# Inputs.net
KiCad netlist of a schematic drawn in Altium Designer
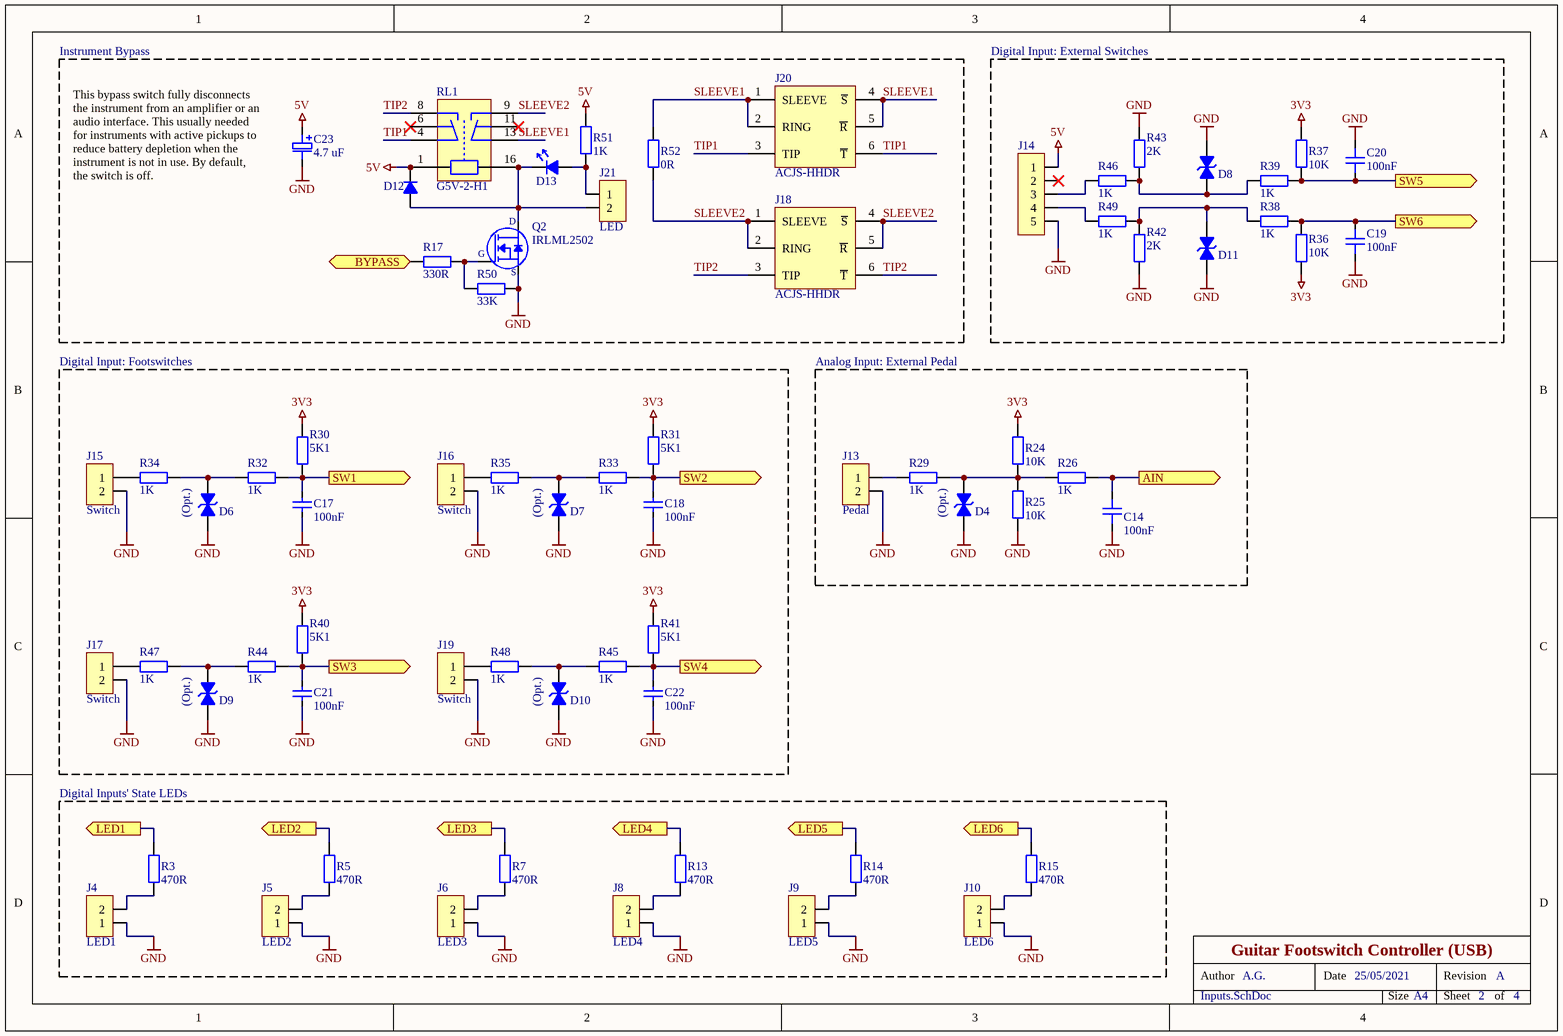
[diagram p0: Inputs.SchDoc]

(export (version "E")
  (design (tool "Eeschema 10.0.6"))
  (components
    (comp (ref "C14")
      (value "100nF")
      (footprint "0603C_RF_M")
      (description "Capacitor")
      (fields (field (name "TOLERANCE") "?") (field (name "MANUFACTURER") "Generic Brand"))
      (libsource (lib "") (part "C_1"))
    )
    (comp (ref "C17")
      (value "100nF")
      (footprint "0603C_RF_M")
      (description "Capacitor")
      (fields (field (name "TOLERANCE") "?") (field (name "MANUFACTURER") "Generic Brand"))
      (libsource (lib "AG.Generic") (part "C"))
    )
    (comp (ref "C18")
      (value "100nF")
      (footprint "0603C_RF_M")
      (description "Capacitor")
      (fields (field (name "TOLERANCE") "?") (field (name "MANUFACTURER") "Generic Brand"))
      (libsource (lib "AG.Generic") (part "C"))
    )
    (comp (ref "C19")
      (value "100nF")
      (footprint "0603C_RF_M")
      (description "Capacitor")
      (fields (field (name "TOLERANCE") "?") (field (name "MANUFACTURER") "Generic Brand"))
      (libsource (lib "") (part "C_1"))
    )
    (comp (ref "C20")
      (value "100nF")
      (footprint "0603C_RF_M")
      (description "Capacitor")
      (fields (field (name "TOLERANCE") "?") (field (name "MANUFACTURER") "Generic Brand"))
      (libsource (lib "") (part "C_1"))
    )
    (comp (ref "C21")
      (value "100nF")
      (footprint "0603C_RF_M")
      (description "Capacitor")
      (fields (field (name "TOLERANCE") "?") (field (name "MANUFACTURER") "Generic Brand"))
      (libsource (lib "AG.Generic") (part "C"))
    )
    (comp (ref "C22")
      (value "100nF")
      (footprint "0603C_RF_M")
      (description "Capacitor")
      (fields (field (name "TOLERANCE") "?") (field (name "MANUFACTURER") "Generic Brand"))
      (libsource (lib "AG.Generic") (part "C"))
    )
    (comp (ref "C23")
      (value "4.7 uF")
      (footprint "C_EL_B_4MM_RF_M")
      (description "Polarized Capacitor")
      (fields (field (name "TOLERANCE") "?") (field (name "MANUFACTURER") "Generic Brand"))
      (libsource (lib "AG.Generic") (part "C-P"))
    )
    (comp (ref "D4")
      (value "TVS")
      (footprint "NXP_SOD-323_RF_M")
      (description "TVS Diode Bidirectional")
      (fields (field (name "MANUFACTURER") "Generic Brand"))
      (libsource (lib "AG.Generic") (part "D-TVS"))
    )
    (comp (ref "D6")
      (value "TVS")
      (footprint "NXP_SOD-323_RF_M")
      (description "TVS Diode Bidirectional")
      (fields (field (name "MANUFACTURER") "Generic Brand"))
      (libsource (lib "AG.Generic") (part "D-TVS"))
    )
    (comp (ref "D7")
      (value "TVS")
      (footprint "NXP_SOD-323_RF_M")
      (description "TVS Diode Bidirectional")
      (fields (field (name "MANUFACTURER") "Generic Brand"))
      (libsource (lib "AG.Generic") (part "D-TVS"))
    )
    (comp (ref "D8")
      (value "TVS")
      (footprint "NXP_SOD-323_RF_M")
      (description "TVS Diode Bidirectional")
      (fields (field (name "MANUFACTURER") "Generic Brand"))
      (libsource (lib "AG.Generic") (part "D-TVS"))
    )
    (comp (ref "D9")
      (value "TVS")
      (footprint "NXP_SOD-323_RF_M")
      (description "TVS Diode Bidirectional")
      (fields (field (name "MANUFACTURER") "Generic Brand"))
      (libsource (lib "AG.Generic") (part "D-TVS"))
    )
    (comp (ref "D10")
      (value "TVS")
      (footprint "NXP_SOD-323_RF_M")
      (description "TVS Diode Bidirectional")
      (fields (field (name "MANUFACTURER") "Generic Brand"))
      (libsource (lib "AG.Generic") (part "D-TVS"))
    )
    (comp (ref "D11")
      (value "TVS")
      (footprint "NXP_SOD-323_RF_M")
      (description "TVS Diode Bidirectional")
      (fields (field (name "MANUFACTURER") "Generic Brand"))
      (libsource (lib "AG.Generic") (part "D-TVS"))
    )
    (comp (ref "D12")
      (value "D")
      (footprint "NXP_SOD-323_RF_M")
      (description "Diode (Rectifier)")
      (fields (field (name "MANUFACTURER") "Generic Brand"))
      (libsource (lib "AG.Generic") (part "D"))
    )
    (comp (ref "D13")
      (value "LED")
      (footprint "0805LED_RF_M")
      (fields (field (name "MANUFACTURER") "Generic Brand"))
      (libsource (lib "AG.Generic") (part "LED"))
    )
    (comp (ref "J4")
      (value "LED1")
      (footprint "AG.Connectors:HEADER-2.54-2P1")
      (description "Generic Pin Header 2x1")
      (libsource (lib "AG.Connectors") (part "PINHDR_2x1"))
    )
    (comp (ref "J5")
      (value "LED2")
      (footprint "AG.Connectors:HEADER-2.54-2P1")
      (description "Generic Pin Header 2x1")
      (libsource (lib "AG.Connectors") (part "PINHDR_2x1"))
    )
    (comp (ref "J6")
      (value "LED3")
      (footprint "AG.Connectors:HEADER-2.54-2P1")
      (description "Generic Pin Header 2x1")
      (libsource (lib "AG.Connectors") (part "PINHDR_2x1"))
    )
    (comp (ref "J8")
      (value "LED4")
      (footprint "AG.Connectors:HEADER-2.54-2P1")
      (description "Generic Pin Header 2x1")
      (libsource (lib "AG.Connectors") (part "PINHDR_2x1"))
    )
    (comp (ref "J9")
      (value "LED5")
      (footprint "AG.Connectors:HEADER-2.54-2P1")
      (description "Generic Pin Header 2x1")
      (libsource (lib "AG.Connectors") (part "PINHDR_2x1"))
    )
    (comp (ref "J10")
      (value "LED6")
      (footprint "AG.Connectors:HEADER-2.54-2P1")
      (description "Generic Pin Header 2x1")
      (libsource (lib "AG.Connectors") (part "PINHDR_2x1"))
    )
    (comp (ref "J13")
      (value "Pedal")
      (footprint "HEADER-2.54-2P1")
      (description "Pin Header Single Row 2 Positions")
      (libsource (lib "AG.Connectors") (part "PINHDR-2P1"))
    )
    (comp (ref "J14")
      (value "PINHDR_5x1")
      (footprint "AG.Connectors:HEADER-2.54-5P1")
      (description "Generic Pin Header 5x1")
      (libsource (lib "AG.Connectors") (part "PINHDR_5x1"))
    )
    (comp (ref "J15")
      (value "Switch")
      (footprint "AG.Connectors:HEADER-2.54-2P1")
      (description "Generic Pin Header 2x1")
      (libsource (lib "") (part "PINHDR_2x1_1"))
    )
    (comp (ref "J16")
      (value "Switch")
      (footprint "AG.Connectors:HEADER-2.54-2P1")
      (description "Generic Pin Header 2x1")
      (libsource (lib "") (part "PINHDR_2x1_1"))
    )
    (comp (ref "J17")
      (value "Switch")
      (footprint "AG.Connectors:HEADER-2.54-2P1")
      (description "Generic Pin Header 2x1")
      (libsource (lib "") (part "PINHDR_2x1_1"))
    )
    (comp (ref "J18")
      (value "ACJS-HHDR")
      (footprint "ACJS-HHDR")
      (description "1/4\" Stereo Jack PCB Receptacle")
      (fields (field (name "MANUFACTURER") "Amphenol") (field (name "ALTERNATIVE SUPPLIER PART NO") "44079"))
      (libsource (lib "AG.Connectors") (part "ACJS-HHDR"))
    )
    (comp (ref "J19")
      (value "Switch")
      (footprint "AG.Connectors:HEADER-2.54-2P1")
      (description "Generic Pin Header 2x1")
      (libsource (lib "") (part "PINHDR_2x1_1"))
    )
    (comp (ref "J20")
      (value "ACJS-HHDR")
      (footprint "ACJS-HHDR")
      (description "1/4\" Stereo Jack PCB Receptacle")
      (fields (field (name "MANUFACTURER") "Amphenol") (field (name "ALTERNATIVE SUPPLIER PART NO") "44079"))
      (libsource (lib "AG.Connectors") (part "ACJS-HHDR"))
    )
    (comp (ref "J21")
      (value "LED")
      (footprint "AG.Connectors:HEADER-2.54-2P1")
      (description "Generic Pin Header 2x1")
      (libsource (lib "") (part "PINHDR_2x1_2"))
    )
    (comp (ref "Q2")
      (value "IRLML2502")
      (footprint "IRLML_SOT-23")
      (description "MOSFET N-CH 20V 4.2A SOT23")
      (fields (field (name "MANUFACTURER") "Infineon") (field (name "MANUFACTURER PART NO") "IRLML2502TRPBF"))
      (libsource (lib "AG.Discrete") (part "IRLML2502"))
    )
    (comp (ref "R3")
      (value "470R")
      (footprint "0603R_RF_M")
      (description "Resistor")
      (fields (field (name "TOLERANCE") "?") (field (name "MANUFACTURER") "Generic Brand"))
      (libsource (lib "AG.Generic") (part "R"))
    )
    (comp (ref "R5")
      (value "470R")
      (footprint "0603R_RF_M")
      (description "Resistor")
      (fields (field (name "TOLERANCE") "?") (field (name "MANUFACTURER") "Generic Brand"))
      (libsource (lib "AG.Generic") (part "R"))
    )
    (comp (ref "R7")
      (value "470R")
      (footprint "0603R_RF_M")
      (description "Resistor")
      (fields (field (name "TOLERANCE") "?") (field (name "MANUFACTURER") "Generic Brand"))
      (libsource (lib "AG.Generic") (part "R"))
    )
    (comp (ref "R13")
      (value "470R")
      (footprint "0603R_RF_M")
      (description "Resistor")
      (fields (field (name "TOLERANCE") "?") (field (name "MANUFACTURER") "Generic Brand"))
      (libsource (lib "AG.Generic") (part "R"))
    )
    (comp (ref "R14")
      (value "470R")
      (footprint "0603R_RF_M")
      (description "Resistor")
      (fields (field (name "TOLERANCE") "?") (field (name "MANUFACTURER") "Generic Brand"))
      (libsource (lib "AG.Generic") (part "R"))
    )
    (comp (ref "R15")
      (value "470R")
      (footprint "0603R_RF_M")
      (description "Resistor")
      (fields (field (name "TOLERANCE") "?") (field (name "MANUFACTURER") "Generic Brand"))
      (libsource (lib "AG.Generic") (part "R"))
    )
    (comp (ref "R17")
      (value "330R")
      (footprint "0603R_RF_M")
      (description "Resistor")
      (fields (field (name "TOLERANCE") "?") (field (name "MANUFACTURER") "Generic Brand"))
      (libsource (lib "AG.Generic") (part "R"))
    )
    (comp (ref "R24")
      (value "10K")
      (footprint "0603R_RF_M")
      (description "Resistor")
      (fields (field (name "TOLERANCE") "?") (field (name "MANUFACTURER") "Generic Brand"))
      (libsource (lib "AG.Generic") (part "R"))
    )
    (comp (ref "R25")
      (value "10K")
      (footprint "0603R_RF_M")
      (description "Resistor")
      (fields (field (name "TOLERANCE") "?") (field (name "MANUFACTURER") "Generic Brand"))
      (libsource (lib "AG.Generic") (part "R"))
    )
    (comp (ref "R26")
      (value "1K")
      (footprint "0603R_RF_M")
      (description "Resistor")
      (fields (field (name "TOLERANCE") "?") (field (name "MANUFACTURER") "Generic Brand"))
      (libsource (lib "AG.Generic") (part "R"))
    )
    (comp (ref "R29")
      (value "1K")
      (footprint "0603R_RF_M")
      (description "Resistor")
      (fields (field (name "TOLERANCE") "?") (field (name "MANUFACTURER") "Generic Brand"))
      (libsource (lib "AG.Generic") (part "R"))
    )
    (comp (ref "R30")
      (value "5K1")
      (footprint "0603R_RF_M")
      (description "Resistor")
      (fields (field (name "TOLERANCE") "?") (field (name "MANUFACTURER") "Generic Brand"))
      (libsource (lib "AG.Generic") (part "R"))
    )
    (comp (ref "R31")
      (value "5K1")
      (footprint "0603R_RF_M")
      (description "Resistor")
      (fields (field (name "TOLERANCE") "?") (field (name "MANUFACTURER") "Generic Brand"))
      (libsource (lib "AG.Generic") (part "R"))
    )
    (comp (ref "R32")
      (value "1K")
      (footprint "0603R_RF_M")
      (description "Resistor")
      (fields (field (name "TOLERANCE") "?") (field (name "MANUFACTURER") "Generic Brand"))
      (libsource (lib "AG.Generic") (part "R"))
    )
    (comp (ref "R33")
      (value "1K")
      (footprint "0603R_RF_M")
      (description "Resistor")
      (fields (field (name "TOLERANCE") "?") (field (name "MANUFACTURER") "Generic Brand"))
      (libsource (lib "AG.Generic") (part "R"))
    )
    (comp (ref "R34")
      (value "1K")
      (footprint "0603R_RF_M")
      (description "Resistor")
      (fields (field (name "TOLERANCE") "?") (field (name "MANUFACTURER") "Generic Brand"))
      (libsource (lib "AG.Generic") (part "R"))
    )
    (comp (ref "R35")
      (value "1K")
      (footprint "0603R_RF_M")
      (description "Resistor")
      (fields (field (name "TOLERANCE") "?") (field (name "MANUFACTURER") "Generic Brand"))
      (libsource (lib "AG.Generic") (part "R"))
    )
    (comp (ref "R36")
      (value "10K")
      (footprint "0603R_RF_M")
      (description "Resistor")
      (fields (field (name "TOLERANCE") "?") (field (name "MANUFACTURER") "Generic Brand"))
      (libsource (lib "AG.Generic") (part "R"))
    )
    (comp (ref "R37")
      (value "10K")
      (footprint "0603R_RF_M")
      (description "Resistor")
      (fields (field (name "TOLERANCE") "?") (field (name "MANUFACTURER") "Generic Brand"))
      (libsource (lib "AG.Generic") (part "R"))
    )
    (comp (ref "R38")
      (value "1K")
      (footprint "0603R_RF_M")
      (description "Resistor")
      (fields (field (name "TOLERANCE") "?") (field (name "MANUFACTURER") "Generic Brand"))
      (libsource (lib "AG.Generic") (part "R"))
    )
    (comp (ref "R39")
      (value "1K")
      (footprint "0603R_RF_M")
      (description "Resistor")
      (fields (field (name "TOLERANCE") "?") (field (name "MANUFACTURER") "Generic Brand"))
      (libsource (lib "AG.Generic") (part "R"))
    )
    (comp (ref "R40")
      (value "5K1")
      (footprint "0603R_RF_M")
      (description "Resistor")
      (fields (field (name "TOLERANCE") "?") (field (name "MANUFACTURER") "Generic Brand"))
      (libsource (lib "AG.Generic") (part "R"))
    )
    (comp (ref "R41")
      (value "5K1")
      (footprint "0603R_RF_M")
      (description "Resistor")
      (fields (field (name "TOLERANCE") "?") (field (name "MANUFACTURER") "Generic Brand"))
      (libsource (lib "AG.Generic") (part "R"))
    )
    (comp (ref "R42")
      (value "2K")
      (footprint "0603R_RF_M")
      (description "Resistor")
      (fields (field (name "TOLERANCE") "?") (field (name "MANUFACTURER") "Generic Brand"))
      (libsource (lib "AG.Generic") (part "R"))
    )
    (comp (ref "R43")
      (value "2K")
      (footprint "0603R_RF_M")
      (description "Resistor")
      (fields (field (name "TOLERANCE") "?") (field (name "MANUFACTURER") "Generic Brand"))
      (libsource (lib "AG.Generic") (part "R"))
    )
    (comp (ref "R44")
      (value "1K")
      (footprint "0603R_RF_M")
      (description "Resistor")
      (fields (field (name "TOLERANCE") "?") (field (name "MANUFACTURER") "Generic Brand"))
      (libsource (lib "AG.Generic") (part "R"))
    )
    (comp (ref "R45")
      (value "1K")
      (footprint "0603R_RF_M")
      (description "Resistor")
      (fields (field (name "TOLERANCE") "?") (field (name "MANUFACTURER") "Generic Brand"))
      (libsource (lib "AG.Generic") (part "R"))
    )
    (comp (ref "R46")
      (value "1K")
      (footprint "0603R_RF_M")
      (description "Resistor")
      (fields (field (name "TOLERANCE") "?") (field (name "MANUFACTURER") "Generic Brand"))
      (libsource (lib "AG.Generic") (part "R"))
    )
    (comp (ref "R47")
      (value "1K")
      (footprint "0603R_RF_M")
      (description "Resistor")
      (fields (field (name "TOLERANCE") "?") (field (name "MANUFACTURER") "Generic Brand"))
      (libsource (lib "AG.Generic") (part "R"))
    )
    (comp (ref "R48")
      (value "1K")
      (footprint "0603R_RF_M")
      (description "Resistor")
      (fields (field (name "TOLERANCE") "?") (field (name "MANUFACTURER") "Generic Brand"))
      (libsource (lib "AG.Generic") (part "R"))
    )
    (comp (ref "R49")
      (value "1K")
      (footprint "0603R_RF_M")
      (description "Resistor")
      (fields (field (name "TOLERANCE") "?") (field (name "MANUFACTURER") "Generic Brand"))
      (libsource (lib "AG.Generic") (part "R"))
    )
    (comp (ref "R50")
      (value "33K")
      (footprint "0603R_RF_M")
      (description "Resistor")
      (fields (field (name "TOLERANCE") "?") (field (name "MANUFACTURER") "Generic Brand"))
      (libsource (lib "AG.Generic") (part "R"))
    )
    (comp (ref "R51")
      (value "1K")
      (footprint "0603R_RF_M")
      (description "Resistor")
      (fields (field (name "TOLERANCE") "?") (field (name "MANUFACTURER") "Generic Brand"))
      (libsource (lib "AG.Generic") (part "R"))
    )
    (comp (ref "R52")
      (value "0R")
      (footprint "0805R_RF_M")
      (description "Resistor")
      (fields (field (name "TOLERANCE") "?") (field (name "MANUFACTURER") "Generic Brand"))
      (libsource (lib "AG.Generic") (part "R"))
    )
    (comp (ref "RL1")
      (value "G5V-2-H1")
      (footprint "G5V-2-H1")
      (description "RELAY GEN PURPOSE DPDT 1A 5VDC")
      (fields (field (name "ALTERNATIVE SUPPLIER PART NO") "32041") (field (name "MANUFACTURER") "Omron"))
      (libsource (lib "AG.Electromechanical") (part "G5V-2-H1"))
    )
  )
  (nets
    (net (code "1") (name "/AIN") (class "Default")
      (node (ref "C14") (pin "2") (pinfunction "2_2") (pintype "passive"))
      (node (ref "R26") (pin "2") (pintype "passive"))
    )
    (net (code "2") (name "/BYPASS") (class "Default") (node (ref "R17") (pin "1") (pintype "passive")))
    (net (code "3") (name "/LED1") (class "Default") (node (ref "R3") (pin "2") (pintype "passive")))
    (net (code "4") (name "/LED2") (class "Default") (node (ref "R5") (pin "2") (pintype "passive")))
    (net (code "5") (name "/LED3") (class "Default") (node (ref "R7") (pin "2") (pintype "passive")))
    (net (code "6") (name "/LED4") (class "Default") (node (ref "R13") (pin "2") (pintype "passive")))
    (net (code "7") (name "/LED5") (class "Default") (node (ref "R14") (pin "2") (pintype "passive")))
    (net (code "8") (name "/LED6") (class "Default") (node (ref "R15") (pin "2") (pintype "passive")))
    (net (code "9") (name "/SLEEVE1") (class "Default")
      (node (ref "J20") (pin "1") (pinfunction "SLEEVE_1") (pintype "passive"))
      (node (ref "J20") (pin "2") (pinfunction "RING_2") (pintype "passive"))
      (node (ref "J20") (pin "4") (pinfunction "~{S}_4") (pintype "passive"))
      (node (ref "J20") (pin "5") (pinfunction "~{R}_5") (pintype "passive"))
      (node (ref "R52") (pin "2") (pintype "passive"))
      (node (ref "RL1") (pin "13") (pinfunction "COM2_13") (pintype "passive"))
    )
    (net (code "10") (name "/SLEEVE2") (class "Default")
      (node (ref "J18") (pin "1") (pinfunction "SLEEVE_1") (pintype "passive"))
      (node (ref "J18") (pin "2") (pinfunction "RING_2") (pintype "passive"))
      (node (ref "J18") (pin "4") (pinfunction "~{S}_4") (pintype "passive"))
      (node (ref "J18") (pin "5") (pinfunction "~{R}_5") (pintype "passive"))
      (node (ref "R52") (pin "1") (pintype "passive"))
      (node (ref "RL1") (pin "9") (pinfunction "NO2_9") (pintype "passive"))
    )
    (net (code "11") (name "/SW1") (class "Default")
      (node (ref "C17") (pin "2") (pinfunction "2_2") (pintype "passive"))
      (node (ref "R30") (pin "2") (pintype "passive"))
      (node (ref "R32") (pin "2") (pintype "passive"))
    )
    (net (code "12") (name "/SW2") (class "Default")
      (node (ref "C18") (pin "2") (pinfunction "2_2") (pintype "passive"))
      (node (ref "R31") (pin "2") (pintype "passive"))
      (node (ref "R33") (pin "2") (pintype "passive"))
    )
    (net (code "13") (name "/SW3") (class "Default")
      (node (ref "C21") (pin "2") (pinfunction "2_2") (pintype "passive"))
      (node (ref "R40") (pin "2") (pintype "passive"))
      (node (ref "R44") (pin "2") (pintype "passive"))
    )
    (net (code "14") (name "/SW4") (class "Default")
      (node (ref "C22") (pin "2") (pinfunction "2_2") (pintype "passive"))
      (node (ref "R41") (pin "2") (pintype "passive"))
      (node (ref "R45") (pin "2") (pintype "passive"))
    )
    (net (code "15") (name "/SW5") (class "Default")
      (node (ref "C20") (pin "2") (pinfunction "2_2") (pintype "passive"))
      (node (ref "R37") (pin "1") (pintype "passive"))
      (node (ref "R39") (pin "2") (pintype "passive"))
    )
    (net (code "16") (name "/SW6") (class "Default")
      (node (ref "C19") (pin "1") (pinfunction "1_1") (pintype "passive"))
      (node (ref "R36") (pin "1") (pintype "passive"))
      (node (ref "R38") (pin "2") (pintype "passive"))
    )
    (net (code "17") (name "/TIP1") (class "Default")
      (node (ref "J20") (pin "3") (pinfunction "TIP_3") (pintype "passive"))
      (node (ref "J20") (pin "6") (pinfunction "~{T}_6") (pintype "passive"))
      (node (ref "RL1") (pin "4") (pinfunction "COM1_4") (pintype "passive"))
    )
    (net (code "18") (name "/TIP2") (class "Default")
      (node (ref "J18") (pin "3") (pinfunction "TIP_3") (pintype "passive"))
      (node (ref "J18") (pin "6") (pinfunction "~{T}_6") (pintype "passive"))
      (node (ref "RL1") (pin "8") (pinfunction "NO1_8") (pintype "passive"))
    )
    (net (code "19") (name "3V3") (class "Default")
      (node (ref "R24") (pin "2") (pintype "passive"))
      (node (ref "R30") (pin "1") (pintype "passive"))
      (node (ref "R31") (pin "1") (pintype "passive"))
      (node (ref "R36") (pin "2") (pintype "passive"))
      (node (ref "R37") (pin "2") (pintype "passive"))
      (node (ref "R40") (pin "1") (pintype "passive"))
      (node (ref "R41") (pin "1") (pintype "passive"))
    )
    (net (code "20") (name "5V") (class "Default")
      (node (ref "C23") (pin "P") (pinfunction "P_P") (pintype "power_in"))
      (node (ref "D12") (pin "C") (pinfunction "C_C") (pintype "passive"))
      (node (ref "J14") (pin "1") (pinfunction "1_1") (pintype "passive"))
      (node (ref "R51") (pin "2") (pintype "passive"))
      (node (ref "RL1") (pin "1") (pinfunction "SW_1") (pintype "passive"))
    )
    (net (code "21") (name "GND") (class "Default")
      (node (ref "C14") (pin "1") (pinfunction "1_1") (pintype "passive"))
      (node (ref "C17") (pin "1") (pinfunction "1_1") (pintype "passive"))
      (node (ref "C18") (pin "1") (pinfunction "1_1") (pintype "passive"))
      (node (ref "C19") (pin "2") (pinfunction "2_2") (pintype "passive"))
      (node (ref "C20") (pin "1") (pinfunction "1_1") (pintype "passive"))
      (node (ref "C21") (pin "1") (pinfunction "1_1") (pintype "passive"))
      (node (ref "C22") (pin "1") (pinfunction "1_1") (pintype "passive"))
      (node (ref "C23") (pin "N") (pinfunction "N_N") (pintype "power_in"))
      (node (ref "D10") (pin "A") (pinfunction "A_A") (pintype "passive"))
      (node (ref "D11") (pin "A") (pinfunction "A_A") (pintype "passive"))
      (node (ref "D4") (pin "A") (pinfunction "A_A") (pintype "passive"))
      (node (ref "D6") (pin "A") (pinfunction "A_A") (pintype "passive"))
      (node (ref "D7") (pin "A") (pinfunction "A_A") (pintype "passive"))
      (node (ref "D8") (pin "A") (pinfunction "A_A") (pintype "passive"))
      (node (ref "D9") (pin "A") (pinfunction "A_A") (pintype "passive"))
      (node (ref "J10") (pin "1") (pinfunction "1_1") (pintype "passive"))
      (node (ref "J13") (pin "2") (pinfunction "2_2") (pintype "passive"))
      (node (ref "J14") (pin "5") (pinfunction "5_5") (pintype "passive"))
      (node (ref "J15") (pin "2") (pinfunction "2_2") (pintype "passive"))
      (node (ref "J16") (pin "2") (pinfunction "2_2") (pintype "passive"))
      (node (ref "J17") (pin "2") (pinfunction "2_2") (pintype "passive"))
      (node (ref "J19") (pin "2") (pinfunction "2_2") (pintype "passive"))
      (node (ref "J4") (pin "1") (pinfunction "1_1") (pintype "passive"))
      (node (ref "J5") (pin "1") (pinfunction "1_1") (pintype "passive"))
      (node (ref "J6") (pin "1") (pinfunction "1_1") (pintype "passive"))
      (node (ref "J8") (pin "1") (pinfunction "1_1") (pintype "passive"))
      (node (ref "J9") (pin "1") (pinfunction "1_1") (pintype "passive"))
      (node (ref "Q2") (pin "2") (pinfunction "S_2") (pintype "passive"))
      (node (ref "R25") (pin "1") (pintype "passive"))
      (node (ref "R42") (pin "2") (pintype "passive"))
      (node (ref "R43") (pin "1") (pintype "passive"))
      (node (ref "R50") (pin "2") (pintype "passive"))
    )
    (net (code "22") (name "Net-(D4-PadC)") (class "Default")
      (node (ref "D4") (pin "C") (pinfunction "C_C") (pintype "passive"))
      (node (ref "R24") (pin "1") (pintype "passive"))
      (node (ref "R25") (pin "2") (pintype "passive"))
      (node (ref "R26") (pin "1") (pintype "passive"))
      (node (ref "R29") (pin "2") (pintype "passive"))
    )
    (net (code "23") (name "Net-(D6-PadC)") (class "Default")
      (node (ref "D6") (pin "C") (pinfunction "C_C") (pintype "passive"))
      (node (ref "R32") (pin "1") (pintype "passive"))
      (node (ref "R34") (pin "2") (pintype "passive"))
    )
    (net (code "24") (name "Net-(D7-PadC)") (class "Default")
      (node (ref "D7") (pin "C") (pinfunction "C_C") (pintype "passive"))
      (node (ref "R33") (pin "1") (pintype "passive"))
      (node (ref "R35") (pin "2") (pintype "passive"))
    )
    (net (code "25") (name "Net-(D8-PadC)") (class "Default")
      (node (ref "D8") (pin "C") (pinfunction "C_C") (pintype "passive"))
      (node (ref "R39") (pin "1") (pintype "passive"))
      (node (ref "R43") (pin "2") (pintype "passive"))
      (node (ref "R46") (pin "2") (pintype "passive"))
    )
    (net (code "26") (name "Net-(D9-PadC)") (class "Default")
      (node (ref "D9") (pin "C") (pinfunction "C_C") (pintype "passive"))
      (node (ref "R44") (pin "1") (pintype "passive"))
      (node (ref "R47") (pin "2") (pintype "passive"))
    )
    (net (code "27") (name "Net-(D10-PadC)") (class "Default")
      (node (ref "D10") (pin "C") (pinfunction "C_C") (pintype "passive"))
      (node (ref "R45") (pin "1") (pintype "passive"))
      (node (ref "R48") (pin "2") (pintype "passive"))
    )
    (net (code "28") (name "Net-(D11-PadC)") (class "Default")
      (node (ref "D11") (pin "C") (pinfunction "C_C") (pintype "passive"))
      (node (ref "R38") (pin "1") (pintype "passive"))
      (node (ref "R42") (pin "1") (pintype "passive"))
      (node (ref "R49") (pin "2") (pintype "passive"))
    )
    (net (code "29") (name "Net-(D13-PadA)") (class "Default")
      (node (ref "D13") (pin "A") (pinfunction "A_A") (pintype "passive"))
      (node (ref "J21") (pin "1") (pinfunction "1_1") (pintype "passive"))
      (node (ref "R51") (pin "1") (pintype "passive"))
    )
    (net (code "30") (name "Net-(J4-Pad2)") (class "Default")
      (node (ref "J4") (pin "2") (pinfunction "2_2") (pintype "passive"))
      (node (ref "R3") (pin "1") (pintype "passive"))
    )
    (net (code "31") (name "Net-(J5-Pad2)") (class "Default")
      (node (ref "J5") (pin "2") (pinfunction "2_2") (pintype "passive"))
      (node (ref "R5") (pin "1") (pintype "passive"))
    )
    (net (code "32") (name "Net-(J6-Pad2)") (class "Default")
      (node (ref "J6") (pin "2") (pinfunction "2_2") (pintype "passive"))
      (node (ref "R7") (pin "1") (pintype "passive"))
    )
    (net (code "33") (name "Net-(J8-Pad2)") (class "Default")
      (node (ref "J8") (pin "2") (pinfunction "2_2") (pintype "passive"))
      (node (ref "R13") (pin "1") (pintype "passive"))
    )
    (net (code "34") (name "Net-(J9-Pad2)") (class "Default")
      (node (ref "J9") (pin "2") (pinfunction "2_2") (pintype "passive"))
      (node (ref "R14") (pin "1") (pintype "passive"))
    )
    (net (code "35") (name "Net-(J10-Pad2)") (class "Default")
      (node (ref "J10") (pin "2") (pinfunction "2_2") (pintype "passive"))
      (node (ref "R15") (pin "1") (pintype "passive"))
    )
    (net (code "36") (name "Net-(J13-Pad1)") (class "Default")
      (node (ref "J13") (pin "1") (pinfunction "1_1") (pintype "passive"))
      (node (ref "R29") (pin "1") (pintype "passive"))
    )
    (net (code "37") (name "Net-(J14-Pad3)") (class "Default")
      (node (ref "J14") (pin "3") (pinfunction "3_3") (pintype "passive"))
      (node (ref "R46") (pin "1") (pintype "passive"))
    )
    (net (code "38") (name "Net-(J14-Pad4)") (class "Default")
      (node (ref "J14") (pin "4") (pinfunction "4_4") (pintype "passive"))
      (node (ref "R49") (pin "1") (pintype "passive"))
    )
    (net (code "39") (name "Net-(J15-Pad1)") (class "Default")
      (node (ref "J15") (pin "1") (pinfunction "1_1") (pintype "passive"))
      (node (ref "R34") (pin "1") (pintype "passive"))
    )
    (net (code "40") (name "Net-(J16-Pad1)") (class "Default")
      (node (ref "J16") (pin "1") (pinfunction "1_1") (pintype "passive"))
      (node (ref "R35") (pin "1") (pintype "passive"))
    )
    (net (code "41") (name "Net-(J17-Pad1)") (class "Default")
      (node (ref "J17") (pin "1") (pinfunction "1_1") (pintype "passive"))
      (node (ref "R47") (pin "1") (pintype "passive"))
    )
    (net (code "42") (name "Net-(J19-Pad1)") (class "Default")
      (node (ref "J19") (pin "1") (pinfunction "1_1") (pintype "passive"))
      (node (ref "R48") (pin "1") (pintype "passive"))
    )
    (net (code "43") (name "Net-(Q2-D)") (class "Default")
      (node (ref "D12") (pin "A") (pinfunction "A_A") (pintype "passive"))
      (node (ref "D13") (pin "C") (pinfunction "C_C") (pintype "passive"))
      (node (ref "J21") (pin "2") (pinfunction "2_2") (pintype "passive"))
      (node (ref "Q2") (pin "3") (pinfunction "D_3") (pintype "passive"))
      (node (ref "RL1") (pin "16") (pinfunction "SW_16") (pintype "passive"))
    )
    (net (code "44") (name "Net-(Q2-G)") (class "Default")
      (node (ref "Q2") (pin "1") (pinfunction "G_1") (pintype "passive"))
      (node (ref "R17") (pin "2") (pintype "passive"))
      (node (ref "R50") (pin "1") (pintype "passive"))
    )
    (net (code "45") (name "unconnected-(J14-Pad2)") (class "Default")
      (node (ref "J14") (pin "2") (pinfunction "2_2") (pintype "passive+no_connect"))
    )
    (net (code "46") (name "unconnected-(RL1-NC1-Pad6)") (class "Default")
      (node (ref "RL1") (pin "6") (pinfunction "NC1_6") (pintype "passive+no_connect"))
    )
    (net (code "47") (name "unconnected-(RL1-NC2-Pad11)") (class "Default")
      (node (ref "RL1") (pin "11") (pinfunction "NC2_11") (pintype "passive+no_connect"))
    )
  )
)
